# Chov2_led.net
KiCad netlist of a schematic drawn in Altium Designer
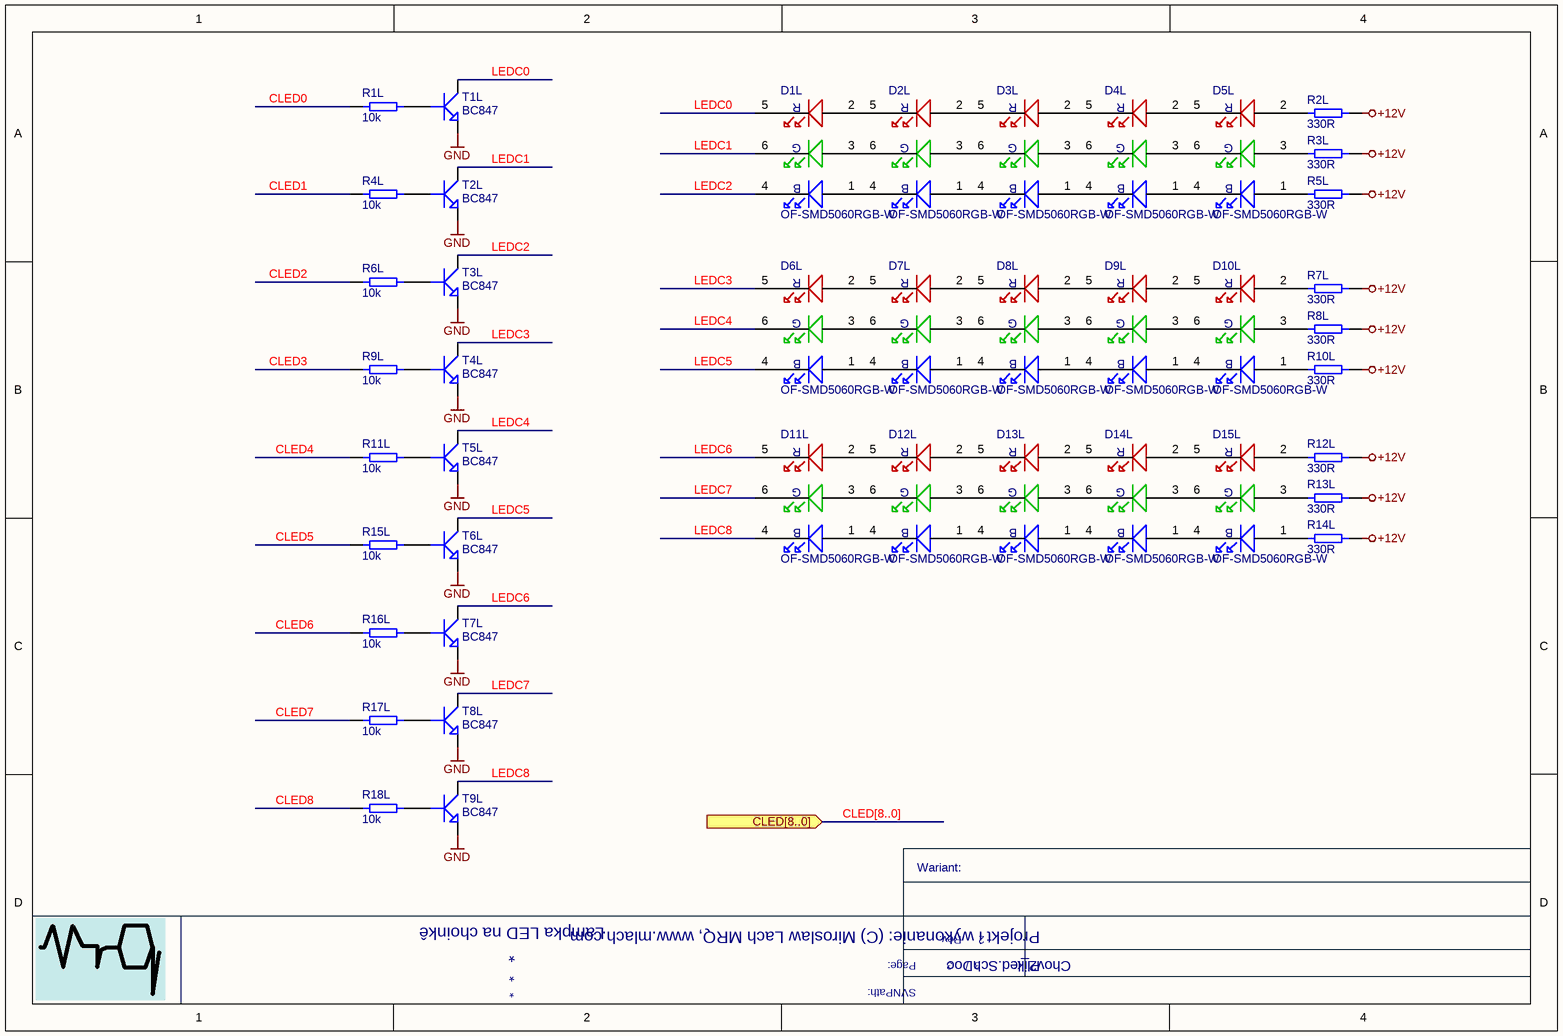
[diagram p0: Chov2_led.SchDoc]

(export (version "E")
  (design (tool "Eeschema 10.0.6"))
  (components
    (comp (ref "D1L")
      (value "OF-SMD5060RGB-W")
      (footprint "OF-SMD5060RGB-W")
      (libsource (lib "Parts") (part "OF-SMD5060RGB-W"))
    )
    (comp (ref "D2L")
      (value "OF-SMD5060RGB-W")
      (footprint "OF-SMD5060RGB-W")
      (libsource (lib "Parts") (part "OF-SMD5060RGB-W"))
    )
    (comp (ref "D3L")
      (value "OF-SMD5060RGB-W")
      (footprint "OF-SMD5060RGB-W")
      (libsource (lib "Parts") (part "OF-SMD5060RGB-W"))
    )
    (comp (ref "D4L")
      (value "OF-SMD5060RGB-W")
      (footprint "OF-SMD5060RGB-W")
      (libsource (lib "Parts") (part "OF-SMD5060RGB-W"))
    )
    (comp (ref "D5L")
      (value "OF-SMD5060RGB-W")
      (footprint "OF-SMD5060RGB-W")
      (libsource (lib "Parts") (part "OF-SMD5060RGB-W"))
    )
    (comp (ref "D6L")
      (value "OF-SMD5060RGB-W")
      (footprint "OF-SMD5060RGB-W")
      (libsource (lib "Parts") (part "OF-SMD5060RGB-W"))
    )
    (comp (ref "D7L")
      (value "OF-SMD5060RGB-W")
      (footprint "OF-SMD5060RGB-W")
      (libsource (lib "Parts") (part "OF-SMD5060RGB-W"))
    )
    (comp (ref "D8L")
      (value "OF-SMD5060RGB-W")
      (footprint "OF-SMD5060RGB-W")
      (libsource (lib "Parts") (part "OF-SMD5060RGB-W"))
    )
    (comp (ref "D9L")
      (value "OF-SMD5060RGB-W")
      (footprint "OF-SMD5060RGB-W")
      (libsource (lib "Parts") (part "OF-SMD5060RGB-W"))
    )
    (comp (ref "D10L")
      (value "OF-SMD5060RGB-W")
      (footprint "OF-SMD5060RGB-W")
      (libsource (lib "Parts") (part "OF-SMD5060RGB-W"))
    )
    (comp (ref "D11L")
      (value "OF-SMD5060RGB-W")
      (footprint "OF-SMD5060RGB-W")
      (libsource (lib "Parts") (part "OF-SMD5060RGB-W"))
    )
    (comp (ref "D12L")
      (value "OF-SMD5060RGB-W")
      (footprint "OF-SMD5060RGB-W")
      (libsource (lib "Parts") (part "OF-SMD5060RGB-W"))
    )
    (comp (ref "D13L")
      (value "OF-SMD5060RGB-W")
      (footprint "OF-SMD5060RGB-W")
      (libsource (lib "Parts") (part "OF-SMD5060RGB-W"))
    )
    (comp (ref "D14L")
      (value "OF-SMD5060RGB-W")
      (footprint "OF-SMD5060RGB-W")
      (libsource (lib "Parts") (part "OF-SMD5060RGB-W"))
    )
    (comp (ref "D15L")
      (value "OF-SMD5060RGB-W")
      (footprint "OF-SMD5060RGB-W")
      (libsource (lib "Parts") (part "OF-SMD5060RGB-W"))
    )
    (comp (ref "R1L")
      (value "0603WGF10KT5E")
      (footprint "0603-IPC")
      (fields (field (name "OTHERPARAMS") "10k") (field (name "TOLERANCE") "1%"))
      (libsource (lib "Parts") (part "R"))
    )
    (comp (ref "R2L")
      (value "0805S8F3300T5E")
      (footprint "0805")
      (fields (field (name "OTHERPARAMS") "330R") (field (name "TOLERANCE") "1%"))
      (libsource (lib "Parts") (part "R"))
    )
    (comp (ref "R3L")
      (value "0805S8F3300T5E")
      (footprint "0805")
      (fields (field (name "OTHERPARAMS") "330R") (field (name "TOLERANCE") "1%"))
      (libsource (lib "Parts") (part "R"))
    )
    (comp (ref "R4L")
      (value "0603WGF10KT5E")
      (footprint "0603-IPC")
      (fields (field (name "OTHERPARAMS") "10k") (field (name "TOLERANCE") "1%"))
      (libsource (lib "Parts") (part "R"))
    )
    (comp (ref "R5L")
      (value "0805S8F3300T5E")
      (footprint "0805")
      (fields (field (name "OTHERPARAMS") "330R") (field (name "TOLERANCE") "1%"))
      (libsource (lib "Parts") (part "R"))
    )
    (comp (ref "R6L")
      (value "0603WGF10KT5E")
      (footprint "0603-IPC")
      (fields (field (name "OTHERPARAMS") "10k") (field (name "TOLERANCE") "1%"))
      (libsource (lib "Parts") (part "R"))
    )
    (comp (ref "R7L")
      (value "0805S8F3300T5E")
      (footprint "0805")
      (fields (field (name "OTHERPARAMS") "330R") (field (name "TOLERANCE") "1%"))
      (libsource (lib "Parts") (part "R"))
    )
    (comp (ref "R8L")
      (value "0805S8F3300T5E")
      (footprint "0805")
      (fields (field (name "OTHERPARAMS") "330R") (field (name "TOLERANCE") "1%"))
      (libsource (lib "Parts") (part "R"))
    )
    (comp (ref "R9L")
      (value "0603WGF10KT5E")
      (footprint "0603-IPC")
      (fields (field (name "OTHERPARAMS") "10k") (field (name "TOLERANCE") "1%"))
      (libsource (lib "Parts") (part "R"))
    )
    (comp (ref "R10L")
      (value "0805S8F3300T5E")
      (footprint "0805")
      (fields (field (name "OTHERPARAMS") "330R") (field (name "TOLERANCE") "1%"))
      (libsource (lib "Parts") (part "R"))
    )
    (comp (ref "R11L")
      (value "0603WGF10KT5E")
      (footprint "0603-IPC")
      (fields (field (name "OTHERPARAMS") "10k") (field (name "TOLERANCE") "1%"))
      (libsource (lib "Parts") (part "R"))
    )
    (comp (ref "R12L")
      (value "0805S8F3300T5E")
      (footprint "0805")
      (fields (field (name "OTHERPARAMS") "330R") (field (name "TOLERANCE") "1%"))
      (libsource (lib "Parts") (part "R"))
    )
    (comp (ref "R13L")
      (value "0805S8F3300T5E")
      (footprint "0805")
      (fields (field (name "OTHERPARAMS") "330R") (field (name "TOLERANCE") "1%"))
      (libsource (lib "Parts") (part "R"))
    )
    (comp (ref "R14L")
      (value "0805S8F3300T5E")
      (footprint "0805")
      (fields (field (name "OTHERPARAMS") "330R") (field (name "TOLERANCE") "1%"))
      (libsource (lib "Parts") (part "R"))
    )
    (comp (ref "R15L")
      (value "0603WGF10KT5E")
      (footprint "0603-IPC")
      (fields (field (name "OTHERPARAMS") "10k") (field (name "TOLERANCE") "1%"))
      (libsource (lib "Parts") (part "R"))
    )
    (comp (ref "R16L")
      (value "0603WGF10KT5E")
      (footprint "0603-IPC")
      (fields (field (name "OTHERPARAMS") "10k") (field (name "TOLERANCE") "1%"))
      (libsource (lib "Parts") (part "R"))
    )
    (comp (ref "R17L")
      (value "0603WGF10KT5E")
      (footprint "0603-IPC")
      (fields (field (name "OTHERPARAMS") "10k") (field (name "TOLERANCE") "1%"))
      (libsource (lib "Parts") (part "R"))
    )
    (comp (ref "R18L")
      (value "0603WGF10KT5E")
      (footprint "0603-IPC")
      (fields (field (name "OTHERPARAMS") "10k") (field (name "TOLERANCE") "1%"))
      (libsource (lib "Parts") (part "R"))
    )
    (comp (ref "T1L") (value "BC847") (footprint "SOT23-3") (libsource (lib "Parts") (part "NPN_SOT23-3")))
    (comp (ref "T2L") (value "BC847") (footprint "SOT23-3") (libsource (lib "Parts") (part "NPN_SOT23-3")))
    (comp (ref "T3L") (value "BC847") (footprint "SOT23-3") (libsource (lib "Parts") (part "NPN_SOT23-3")))
    (comp (ref "T4L") (value "BC847") (footprint "SOT23-3") (libsource (lib "Parts") (part "NPN_SOT23-3")))
    (comp (ref "T5L") (value "BC847") (footprint "SOT23-3") (libsource (lib "Parts") (part "NPN_SOT23-3")))
    (comp (ref "T6L") (value "BC847") (footprint "SOT23-3") (libsource (lib "Parts") (part "NPN_SOT23-3")))
    (comp (ref "T7L") (value "BC847") (footprint "SOT23-3") (libsource (lib "Parts") (part "NPN_SOT23-3")))
    (comp (ref "T8L") (value "BC847") (footprint "SOT23-3") (libsource (lib "Parts") (part "NPN_SOT23-3")))
    (comp (ref "T9L") (value "BC847") (footprint "SOT23-3") (libsource (lib "Parts") (part "NPN_SOT23-3")))
  )
  (nets
    (net (code "1") (name "+12V") (class "Default")
      (node (ref "R10L") (pin "2") (pinfunction "2_2") (pintype "passive"))
      (node (ref "R12L") (pin "2") (pinfunction "2_2") (pintype "passive"))
      (node (ref "R13L") (pin "2") (pinfunction "2_2") (pintype "passive"))
      (node (ref "R14L") (pin "2") (pinfunction "2_2") (pintype "passive"))
      (node (ref "R2L") (pin "2") (pinfunction "2_2") (pintype "passive"))
      (node (ref "R3L") (pin "2") (pinfunction "2_2") (pintype "passive"))
      (node (ref "R5L") (pin "2") (pinfunction "2_2") (pintype "passive"))
      (node (ref "R7L") (pin "2") (pinfunction "2_2") (pintype "passive"))
      (node (ref "R8L") (pin "2") (pinfunction "2_2") (pintype "passive"))
    )
    (net (code "2") (name "/CLED0") (class "Default")
      (node (ref "R1L") (pin "1") (pinfunction "1_1") (pintype "passive"))
    )
    (net (code "3") (name "/CLED1") (class "Default")
      (node (ref "R4L") (pin "1") (pinfunction "1_1") (pintype "passive"))
    )
    (net (code "4") (name "/CLED2") (class "Default")
      (node (ref "R6L") (pin "1") (pinfunction "1_1") (pintype "passive"))
    )
    (net (code "5") (name "/CLED3") (class "Default")
      (node (ref "R9L") (pin "1") (pinfunction "1_1") (pintype "passive"))
    )
    (net (code "6") (name "/CLED4") (class "Default")
      (node (ref "R11L") (pin "1") (pinfunction "1_1") (pintype "passive"))
    )
    (net (code "7") (name "/CLED5") (class "Default")
      (node (ref "R15L") (pin "1") (pinfunction "1_1") (pintype "passive"))
    )
    (net (code "8") (name "/CLED6") (class "Default")
      (node (ref "R16L") (pin "1") (pinfunction "1_1") (pintype "passive"))
    )
    (net (code "9") (name "/CLED7") (class "Default")
      (node (ref "R17L") (pin "1") (pinfunction "1_1") (pintype "passive"))
    )
    (net (code "10") (name "/CLED8") (class "Default")
      (node (ref "R18L") (pin "1") (pinfunction "1_1") (pintype "passive"))
    )
    (net (code "12") (name "/LEDC0") (class "Default")
      (node (ref "D1L") (pin "5") (pinfunction "CATH_5") (pintype "passive"))
      (node (ref "T1L") (pin "3") (pinfunction "3_3") (pintype "passive"))
    )
    (net (code "13") (name "/LEDC1") (class "Default")
      (node (ref "D1L") (pin "6") (pinfunction "CATH_6") (pintype "passive"))
      (node (ref "T2L") (pin "3") (pinfunction "3_3") (pintype "passive"))
    )
    (net (code "14") (name "/LEDC2") (class "Default")
      (node (ref "D1L") (pin "4") (pinfunction "CATH_4") (pintype "passive"))
      (node (ref "T3L") (pin "3") (pinfunction "3_3") (pintype "passive"))
    )
    (net (code "15") (name "/LEDC3") (class "Default")
      (node (ref "D6L") (pin "5") (pinfunction "CATH_5") (pintype "passive"))
      (node (ref "T4L") (pin "3") (pinfunction "3_3") (pintype "passive"))
    )
    (net (code "16") (name "/LEDC4") (class "Default")
      (node (ref "D6L") (pin "6") (pinfunction "CATH_6") (pintype "passive"))
      (node (ref "T5L") (pin "3") (pinfunction "3_3") (pintype "passive"))
    )
    (net (code "17") (name "/LEDC5") (class "Default")
      (node (ref "D6L") (pin "4") (pinfunction "CATH_4") (pintype "passive"))
      (node (ref "T6L") (pin "3") (pinfunction "3_3") (pintype "passive"))
    )
    (net (code "18") (name "/LEDC6") (class "Default")
      (node (ref "D11L") (pin "5") (pinfunction "CATH_5") (pintype "passive"))
      (node (ref "T7L") (pin "3") (pinfunction "3_3") (pintype "passive"))
    )
    (net (code "19") (name "/LEDC7") (class "Default")
      (node (ref "D11L") (pin "6") (pinfunction "CATH_6") (pintype "passive"))
      (node (ref "T8L") (pin "3") (pinfunction "3_3") (pintype "passive"))
    )
    (net (code "20") (name "/LEDC8") (class "Default")
      (node (ref "D11L") (pin "4") (pinfunction "CATH_4") (pintype "passive"))
      (node (ref "T9L") (pin "3") (pinfunction "3_3") (pintype "passive"))
    )
    (net (code "21") (name "GND") (class "Default")
      (node (ref "T1L") (pin "2") (pinfunction "2_2") (pintype "passive"))
      (node (ref "T2L") (pin "2") (pinfunction "2_2") (pintype "passive"))
      (node (ref "T3L") (pin "2") (pinfunction "2_2") (pintype "passive"))
      (node (ref "T4L") (pin "2") (pinfunction "2_2") (pintype "passive"))
      (node (ref "T5L") (pin "2") (pinfunction "2_2") (pintype "passive"))
      (node (ref "T6L") (pin "2") (pinfunction "2_2") (pintype "passive"))
      (node (ref "T7L") (pin "2") (pinfunction "2_2") (pintype "passive"))
      (node (ref "T8L") (pin "2") (pinfunction "2_2") (pintype "passive"))
      (node (ref "T9L") (pin "2") (pinfunction "2_2") (pintype "passive"))
    )
    (net (code "22") (name "Net-(D1L-ANOD-Pad1)") (class "Default")
      (node (ref "D1L") (pin "1") (pinfunction "ANOD_1") (pintype "passive"))
      (node (ref "D2L") (pin "4") (pinfunction "CATH_4") (pintype "passive"))
    )
    (net (code "23") (name "Net-(D1L-ANOD-Pad2)") (class "Default")
      (node (ref "D1L") (pin "2") (pinfunction "ANOD_2") (pintype "passive"))
      (node (ref "D2L") (pin "5") (pinfunction "CATH_5") (pintype "passive"))
    )
    (net (code "24") (name "Net-(D1L-ANOD-Pad3)") (class "Default")
      (node (ref "D1L") (pin "3") (pinfunction "ANOD_3") (pintype "passive"))
      (node (ref "D2L") (pin "6") (pinfunction "CATH_6") (pintype "passive"))
    )
    (net (code "25") (name "Net-(D2L-ANOD-Pad1)") (class "Default")
      (node (ref "D2L") (pin "1") (pinfunction "ANOD_1") (pintype "passive"))
      (node (ref "D3L") (pin "4") (pinfunction "CATH_4") (pintype "passive"))
    )
    (net (code "26") (name "Net-(D2L-ANOD-Pad2)") (class "Default")
      (node (ref "D2L") (pin "2") (pinfunction "ANOD_2") (pintype "passive"))
      (node (ref "D3L") (pin "5") (pinfunction "CATH_5") (pintype "passive"))
    )
    (net (code "27") (name "Net-(D2L-ANOD-Pad3)") (class "Default")
      (node (ref "D2L") (pin "3") (pinfunction "ANOD_3") (pintype "passive"))
      (node (ref "D3L") (pin "6") (pinfunction "CATH_6") (pintype "passive"))
    )
    (net (code "28") (name "Net-(D3L-ANOD-Pad1)") (class "Default")
      (node (ref "D3L") (pin "1") (pinfunction "ANOD_1") (pintype "passive"))
      (node (ref "D4L") (pin "4") (pinfunction "CATH_4") (pintype "passive"))
    )
    (net (code "29") (name "Net-(D3L-ANOD-Pad2)") (class "Default")
      (node (ref "D3L") (pin "2") (pinfunction "ANOD_2") (pintype "passive"))
      (node (ref "D4L") (pin "5") (pinfunction "CATH_5") (pintype "passive"))
    )
    (net (code "30") (name "Net-(D3L-ANOD-Pad3)") (class "Default")
      (node (ref "D3L") (pin "3") (pinfunction "ANOD_3") (pintype "passive"))
      (node (ref "D4L") (pin "6") (pinfunction "CATH_6") (pintype "passive"))
    )
    (net (code "31") (name "Net-(D4L-ANOD-Pad1)") (class "Default")
      (node (ref "D4L") (pin "1") (pinfunction "ANOD_1") (pintype "passive"))
      (node (ref "D5L") (pin "4") (pinfunction "CATH_4") (pintype "passive"))
    )
    (net (code "32") (name "Net-(D4L-ANOD-Pad2)") (class "Default")
      (node (ref "D4L") (pin "2") (pinfunction "ANOD_2") (pintype "passive"))
      (node (ref "D5L") (pin "5") (pinfunction "CATH_5") (pintype "passive"))
    )
    (net (code "33") (name "Net-(D4L-ANOD-Pad3)") (class "Default")
      (node (ref "D4L") (pin "3") (pinfunction "ANOD_3") (pintype "passive"))
      (node (ref "D5L") (pin "6") (pinfunction "CATH_6") (pintype "passive"))
    )
    (net (code "34") (name "Net-(D5L-ANOD-Pad1)") (class "Default")
      (node (ref "D5L") (pin "1") (pinfunction "ANOD_1") (pintype "passive"))
      (node (ref "R5L") (pin "1") (pinfunction "1_1") (pintype "passive"))
    )
    (net (code "35") (name "Net-(D5L-ANOD-Pad2)") (class "Default")
      (node (ref "D5L") (pin "2") (pinfunction "ANOD_2") (pintype "passive"))
      (node (ref "R2L") (pin "1") (pinfunction "1_1") (pintype "passive"))
    )
    (net (code "36") (name "Net-(D5L-ANOD-Pad3)") (class "Default")
      (node (ref "D5L") (pin "3") (pinfunction "ANOD_3") (pintype "passive"))
      (node (ref "R3L") (pin "1") (pinfunction "1_1") (pintype "passive"))
    )
    (net (code "37") (name "Net-(D6L-ANOD-Pad1)") (class "Default")
      (node (ref "D6L") (pin "1") (pinfunction "ANOD_1") (pintype "passive"))
      (node (ref "D7L") (pin "4") (pinfunction "CATH_4") (pintype "passive"))
    )
    (net (code "38") (name "Net-(D6L-ANOD-Pad2)") (class "Default")
      (node (ref "D6L") (pin "2") (pinfunction "ANOD_2") (pintype "passive"))
      (node (ref "D7L") (pin "5") (pinfunction "CATH_5") (pintype "passive"))
    )
    (net (code "39") (name "Net-(D6L-ANOD-Pad3)") (class "Default")
      (node (ref "D6L") (pin "3") (pinfunction "ANOD_3") (pintype "passive"))
      (node (ref "D7L") (pin "6") (pinfunction "CATH_6") (pintype "passive"))
    )
    (net (code "40") (name "Net-(D7L-ANOD-Pad1)") (class "Default")
      (node (ref "D7L") (pin "1") (pinfunction "ANOD_1") (pintype "passive"))
      (node (ref "D8L") (pin "4") (pinfunction "CATH_4") (pintype "passive"))
    )
    (net (code "41") (name "Net-(D7L-ANOD-Pad2)") (class "Default")
      (node (ref "D7L") (pin "2") (pinfunction "ANOD_2") (pintype "passive"))
      (node (ref "D8L") (pin "5") (pinfunction "CATH_5") (pintype "passive"))
    )
    (net (code "42") (name "Net-(D7L-ANOD-Pad3)") (class "Default")
      (node (ref "D7L") (pin "3") (pinfunction "ANOD_3") (pintype "passive"))
      (node (ref "D8L") (pin "6") (pinfunction "CATH_6") (pintype "passive"))
    )
    (net (code "43") (name "Net-(D8L-ANOD-Pad1)") (class "Default")
      (node (ref "D8L") (pin "1") (pinfunction "ANOD_1") (pintype "passive"))
      (node (ref "D9L") (pin "4") (pinfunction "CATH_4") (pintype "passive"))
    )
    (net (code "44") (name "Net-(D8L-ANOD-Pad2)") (class "Default")
      (node (ref "D8L") (pin "2") (pinfunction "ANOD_2") (pintype "passive"))
      (node (ref "D9L") (pin "5") (pinfunction "CATH_5") (pintype "passive"))
    )
    (net (code "45") (name "Net-(D8L-ANOD-Pad3)") (class "Default")
      (node (ref "D8L") (pin "3") (pinfunction "ANOD_3") (pintype "passive"))
      (node (ref "D9L") (pin "6") (pinfunction "CATH_6") (pintype "passive"))
    )
    (net (code "46") (name "Net-(D10L-ANOD-Pad1)") (class "Default")
      (node (ref "D10L") (pin "1") (pinfunction "ANOD_1") (pintype "passive"))
      (node (ref "R10L") (pin "1") (pinfunction "1_1") (pintype "passive"))
    )
    (net (code "47") (name "Net-(D10L-ANOD-Pad2)") (class "Default")
      (node (ref "D10L") (pin "2") (pinfunction "ANOD_2") (pintype "passive"))
      (node (ref "R7L") (pin "1") (pinfunction "1_1") (pintype "passive"))
    )
    (net (code "48") (name "Net-(D10L-ANOD-Pad3)") (class "Default")
      (node (ref "D10L") (pin "3") (pinfunction "ANOD_3") (pintype "passive"))
      (node (ref "R8L") (pin "1") (pinfunction "1_1") (pintype "passive"))
    )
    (net (code "49") (name "Net-(D10L-CATH-Pad4)") (class "Default")
      (node (ref "D10L") (pin "4") (pinfunction "CATH_4") (pintype "passive"))
      (node (ref "D9L") (pin "1") (pinfunction "ANOD_1") (pintype "passive"))
    )
    (net (code "50") (name "Net-(D10L-CATH-Pad5)") (class "Default")
      (node (ref "D10L") (pin "5") (pinfunction "CATH_5") (pintype "passive"))
      (node (ref "D9L") (pin "2") (pinfunction "ANOD_2") (pintype "passive"))
    )
    (net (code "51") (name "Net-(D10L-CATH-Pad6)") (class "Default")
      (node (ref "D10L") (pin "6") (pinfunction "CATH_6") (pintype "passive"))
      (node (ref "D9L") (pin "3") (pinfunction "ANOD_3") (pintype "passive"))
    )
    (net (code "52") (name "Net-(D11L-ANOD-Pad1)") (class "Default")
      (node (ref "D11L") (pin "1") (pinfunction "ANOD_1") (pintype "passive"))
      (node (ref "D12L") (pin "4") (pinfunction "CATH_4") (pintype "passive"))
    )
    (net (code "53") (name "Net-(D11L-ANOD-Pad2)") (class "Default")
      (node (ref "D11L") (pin "2") (pinfunction "ANOD_2") (pintype "passive"))
      (node (ref "D12L") (pin "5") (pinfunction "CATH_5") (pintype "passive"))
    )
    (net (code "54") (name "Net-(D11L-ANOD-Pad3)") (class "Default")
      (node (ref "D11L") (pin "3") (pinfunction "ANOD_3") (pintype "passive"))
      (node (ref "D12L") (pin "6") (pinfunction "CATH_6") (pintype "passive"))
    )
    (net (code "55") (name "Net-(D12L-ANOD-Pad1)") (class "Default")
      (node (ref "D12L") (pin "1") (pinfunction "ANOD_1") (pintype "passive"))
      (node (ref "D13L") (pin "4") (pinfunction "CATH_4") (pintype "passive"))
    )
    (net (code "56") (name "Net-(D12L-ANOD-Pad2)") (class "Default")
      (node (ref "D12L") (pin "2") (pinfunction "ANOD_2") (pintype "passive"))
      (node (ref "D13L") (pin "5") (pinfunction "CATH_5") (pintype "passive"))
    )
    (net (code "57") (name "Net-(D12L-ANOD-Pad3)") (class "Default")
      (node (ref "D12L") (pin "3") (pinfunction "ANOD_3") (pintype "passive"))
      (node (ref "D13L") (pin "6") (pinfunction "CATH_6") (pintype "passive"))
    )
    (net (code "58") (name "Net-(D13L-ANOD-Pad1)") (class "Default")
      (node (ref "D13L") (pin "1") (pinfunction "ANOD_1") (pintype "passive"))
      (node (ref "D14L") (pin "4") (pinfunction "CATH_4") (pintype "passive"))
    )
    (net (code "59") (name "Net-(D13L-ANOD-Pad2)") (class "Default")
      (node (ref "D13L") (pin "2") (pinfunction "ANOD_2") (pintype "passive"))
      (node (ref "D14L") (pin "5") (pinfunction "CATH_5") (pintype "passive"))
    )
    (net (code "60") (name "Net-(D13L-ANOD-Pad3)") (class "Default")
      (node (ref "D13L") (pin "3") (pinfunction "ANOD_3") (pintype "passive"))
      (node (ref "D14L") (pin "6") (pinfunction "CATH_6") (pintype "passive"))
    )
    (net (code "61") (name "Net-(D14L-ANOD-Pad1)") (class "Default")
      (node (ref "D14L") (pin "1") (pinfunction "ANOD_1") (pintype "passive"))
      (node (ref "D15L") (pin "4") (pinfunction "CATH_4") (pintype "passive"))
    )
    (net (code "62") (name "Net-(D14L-ANOD-Pad2)") (class "Default")
      (node (ref "D14L") (pin "2") (pinfunction "ANOD_2") (pintype "passive"))
      (node (ref "D15L") (pin "5") (pinfunction "CATH_5") (pintype "passive"))
    )
    (net (code "63") (name "Net-(D14L-ANOD-Pad3)") (class "Default")
      (node (ref "D14L") (pin "3") (pinfunction "ANOD_3") (pintype "passive"))
      (node (ref "D15L") (pin "6") (pinfunction "CATH_6") (pintype "passive"))
    )
    (net (code "64") (name "Net-(D15L-ANOD-Pad1)") (class "Default")
      (node (ref "D15L") (pin "1") (pinfunction "ANOD_1") (pintype "passive"))
      (node (ref "R14L") (pin "1") (pinfunction "1_1") (pintype "passive"))
    )
    (net (code "65") (name "Net-(D15L-ANOD-Pad2)") (class "Default")
      (node (ref "D15L") (pin "2") (pinfunction "ANOD_2") (pintype "passive"))
      (node (ref "R12L") (pin "1") (pinfunction "1_1") (pintype "passive"))
    )
    (net (code "66") (name "Net-(D15L-ANOD-Pad3)") (class "Default")
      (node (ref "D15L") (pin "3") (pinfunction "ANOD_3") (pintype "passive"))
      (node (ref "R13L") (pin "1") (pinfunction "1_1") (pintype "passive"))
    )
    (net (code "67") (name "Net-(R1L-Pad2)") (class "Default")
      (node (ref "R1L") (pin "2") (pinfunction "2_2") (pintype "passive"))
      (node (ref "T1L") (pin "1") (pinfunction "1_1") (pintype "passive"))
    )
    (net (code "68") (name "Net-(R4L-Pad2)") (class "Default")
      (node (ref "R4L") (pin "2") (pinfunction "2_2") (pintype "passive"))
      (node (ref "T2L") (pin "1") (pinfunction "1_1") (pintype "passive"))
    )
    (net (code "69") (name "Net-(R6L-Pad2)") (class "Default")
      (node (ref "R6L") (pin "2") (pinfunction "2_2") (pintype "passive"))
      (node (ref "T3L") (pin "1") (pinfunction "1_1") (pintype "passive"))
    )
    (net (code "70") (name "Net-(R9L-Pad2)") (class "Default")
      (node (ref "R9L") (pin "2") (pinfunction "2_2") (pintype "passive"))
      (node (ref "T4L") (pin "1") (pinfunction "1_1") (pintype "passive"))
    )
    (net (code "71") (name "Net-(R11L-Pad2)") (class "Default")
      (node (ref "R11L") (pin "2") (pinfunction "2_2") (pintype "passive"))
      (node (ref "T5L") (pin "1") (pinfunction "1_1") (pintype "passive"))
    )
    (net (code "72") (name "Net-(R15L-Pad2)") (class "Default")
      (node (ref "R15L") (pin "2") (pinfunction "2_2") (pintype "passive"))
      (node (ref "T6L") (pin "1") (pinfunction "1_1") (pintype "passive"))
    )
    (net (code "73") (name "Net-(R16L-Pad2)") (class "Default")
      (node (ref "R16L") (pin "2") (pinfunction "2_2") (pintype "passive"))
      (node (ref "T7L") (pin "1") (pinfunction "1_1") (pintype "passive"))
    )
    (net (code "74") (name "Net-(R17L-Pad2)") (class "Default")
      (node (ref "R17L") (pin "2") (pinfunction "2_2") (pintype "passive"))
      (node (ref "T8L") (pin "1") (pinfunction "1_1") (pintype "passive"))
    )
    (net (code "75") (name "Net-(R18L-Pad2)") (class "Default")
      (node (ref "R18L") (pin "2") (pinfunction "2_2") (pintype "passive"))
      (node (ref "T9L") (pin "1") (pinfunction "1_1") (pintype "passive"))
    )
  )
)
